# H16R7x_Frontend_1.net
KiCad netlist of a schematic drawn in Altium Designer
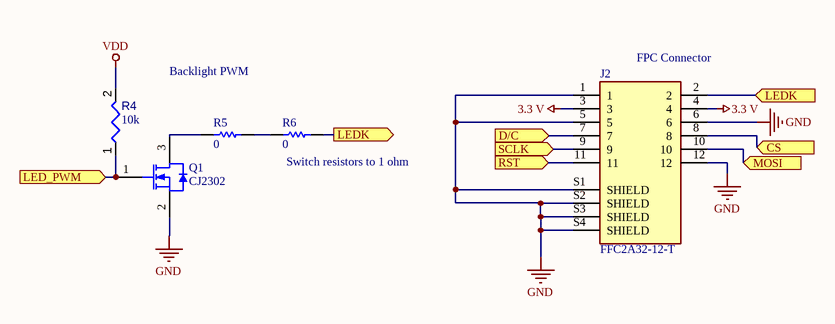
[diagram p0: H16R7x_Frontend 1.SchDoc]

(export (version "E")
  (design (tool "Eeschema 10.0.6"))
  (components
    (comp (ref "J2")
      (value "FFC2A32-12-T")
      (footprint "GCT_FFC2A32-12-T")
      (description "12 Position FFC, FPC Connector Contacts, Vertical - 1 Sided 0.020 (0.50mm) Surface Mount")
      (fields (field (name "MF") "Global Connector Technology"))
      (libsource (lib "Hannah Nguyen") (part "FFC2A32-12-T"))
    )
    (comp (ref "Q1")
      (value "CJ2302")
      (footprint "JSCJ-SOT23-3_V")
      (description "N-Channe Plastic Encapsulate MOSFET, 20 V, 2.1 A, 3-Pin SOT23, Tape and Reel")
      (fields (field (name "MANUFACTURER") "Jiangsu Changjiang Electronics Technology"))
      (libsource (lib "Hannah Nguyen") (part "NEMOS-GSD-3"))
    )
    (comp (ref "R4")
      (value "10k")
      (footprint "RESC0402(1005)_L")
      (description "10K 0.063W 1% 0402 (1005 Metric)  SMD")
      (fields (field (name "POWER") "63mW") (field (name "TOLERANCE") "1%"))
      (libsource (lib "Hannah Nguyen") (part "10KR2F"))
    )
    (comp (ref "R5")
      (value "0")
      (footprint "RESC2013X50X35ML15T15")
      (description "Chip Resistor, 0 Ohm, +/- 1%, 125 mW, -55 to 155 degC, 0805 (2012 Metric)")
      (fields (field (name "TOLERANCE") "1%") (field (name "POWER") "125mW"))
      (libsource (lib "Hannah Nguyen") (part "RES-2"))
    )
    (comp (ref "R6")
      (value "0")
      (footprint "RESC2013X50X35ML15T15")
      (description "Chip Resistor, 0 Ohm, +/- 1%, 125 mW, -55 to 155 degC, 0805 (2012 Metric)")
      (fields (field (name "TOLERANCE") "1%") (field (name "POWER") "125mW"))
      (libsource (lib "Hannah Nguyen") (part "RES-2"))
    )
  )
  (nets
    (net (code "1") (name "/CS") (class "Default")
      (node (ref "J2") (pin "8") (pinfunction "8_8") (pintype "passive"))
    )
    (net (code "2") (name "/D{slash}C") (class "Default")
      (node (ref "J2") (pin "7") (pinfunction "7_7") (pintype "passive"))
    )
    (net (code "3") (name "/LEDK") (class "Default")
      (node (ref "J2") (pin "2") (pinfunction "2_2") (pintype "passive"))
      (node (ref "R6") (pin "2") (pinfunction "2_2") (pintype "passive"))
    )
    (net (code "4") (name "/LED_PWM") (class "Default")
      (node (ref "Q1") (pin "1") (pinfunction "G_1") (pintype "passive"))
      (node (ref "R4") (pin "1") (pinfunction "1_1") (pintype "passive"))
    )
    (net (code "5") (name "/MOSI") (class "Default")
      (node (ref "J2") (pin "10") (pinfunction "10_10") (pintype "passive"))
    )
    (net (code "6") (name "/RST") (class "Default")
      (node (ref "J2") (pin "11") (pinfunction "11_11") (pintype "passive"))
    )
    (net (code "7") (name "/SCLK") (class "Default")
      (node (ref "J2") (pin "9") (pinfunction "9_9") (pintype "passive"))
    )
    (net (code "8") (name "3.3 V") (class "Default")
      (node (ref "J2") (pin "3") (pinfunction "3_3") (pintype "passive"))
      (node (ref "J2") (pin "4") (pinfunction "4_4") (pintype "passive"))
    )
    (net (code "9") (name "GND") (class "Default")
      (node (ref "J2") (pin "1") (pinfunction "1_1") (pintype "passive"))
      (node (ref "J2") (pin "12") (pinfunction "12_12") (pintype "passive"))
      (node (ref "J2") (pin "5") (pinfunction "5_5") (pintype "passive"))
      (node (ref "J2") (pin "6") (pinfunction "6_6") (pintype "passive"))
      (node (ref "J2") (pin "S1") (pinfunction "SHIELD_S1") (pintype "passive"))
      (node (ref "J2") (pin "S2") (pinfunction "SHIELD_S2") (pintype "passive"))
      (node (ref "J2") (pin "S3") (pinfunction "SHIELD_S3") (pintype "passive"))
      (node (ref "J2") (pin "S4") (pinfunction "SHIELD_S4") (pintype "passive"))
      (node (ref "Q1") (pin "2") (pinfunction "S_2") (pintype "passive"))
    )
    (net (code "10") (name "Net-(Q1-D)") (class "Default")
      (node (ref "Q1") (pin "3") (pinfunction "D_3") (pintype "passive"))
      (node (ref "R5") (pin "1") (pinfunction "1_1") (pintype "passive"))
    )
    (net (code "11") (name "Net-(R5-Pad2)") (class "Default")
      (node (ref "R5") (pin "2") (pinfunction "2_2") (pintype "passive"))
      (node (ref "R6") (pin "1") (pinfunction "1_1") (pintype "passive"))
    )
    (net (code "12") (name "VDD") (class "Default")
      (node (ref "R4") (pin "2") (pinfunction "2_2") (pintype "passive"))
    )
  )
)
